# Logic.net
KiCad netlist of a schematic drawn in EAGLE
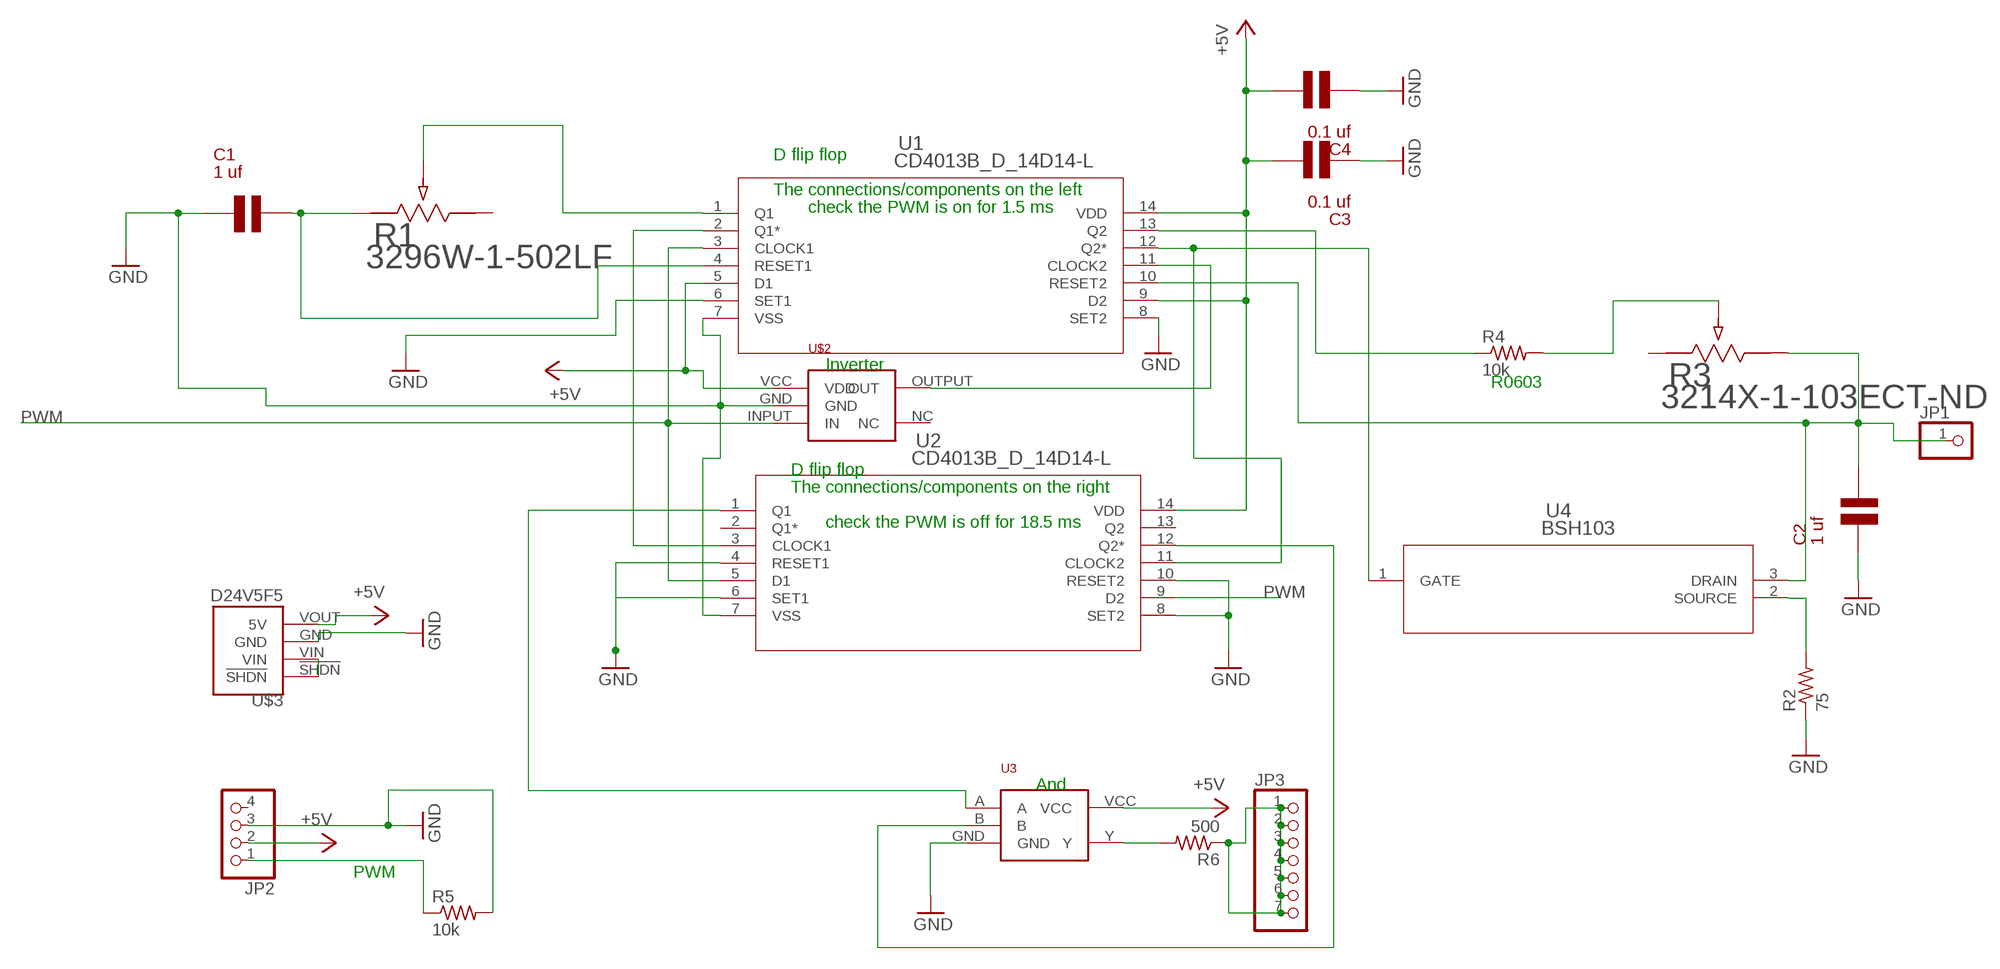
[diagram p0: schematic, sheet 1]

(export (version "E")
  (design (tool "Eeschema 10.0.6"))
  (components
    (comp (ref "C1")
      (value "1 uf")
      (footprint "eagle-import:X7R0805")
      (libsource (lib "eagle-import") (part "CER-CAP"))
    )
    (comp (ref "C2")
      (value "1 uf")
      (footprint "eagle-import:X7R0805")
      (libsource (lib "eagle-import") (part "CER-CAP"))
    )
    (comp (ref "C3")
      (value "0.1 uf")
      (footprint "eagle-import:X7R0805")
      (libsource (lib "eagle-import") (part "CER-CAP"))
    )
    (comp (ref "C4")
      (value "0.1 uf")
      (footprint "eagle-import:X7R0805")
      (libsource (lib "eagle-import") (part "CER-CAP"))
    )
    (comp (ref "JP1")
      (value "PINHD-1X1")
      (footprint "eagle-import:1X01")
      (libsource (lib "eagle-import") (part "PINHD-1X1"))
    )
    (comp (ref "JP2")
      (value "PINHD-1X4")
      (footprint "eagle-import:1X04")
      (libsource (lib "eagle-import") (part "PINHD-1X4"))
    )
    (comp (ref "JP3")
      (value "PINHD-1X7")
      (footprint "eagle-import:1X07")
      (libsource (lib "eagle-import") (part "PINHD-1X7"))
    )
    (comp (ref "R1")
      (value "3296W-1-502LF")
      (footprint "eagle-import:POT_3296W")
      (fields (field (name "MANUFACTURER_PART_NUMBER") "3296W1502LF"))
      (libsource (lib "eagle-import") (part "3296W-1-502LF"))
    )
    (comp (ref "R2")
      (value "75")
      (footprint "eagle-import:R0603")
      (libsource (lib "eagle-import") (part "R-US_R0603"))
    )
    (comp (ref "R3")
      (value "3214X-1-103ECT-ND")
      (footprint "eagle-import:POT_3214X")
      (libsource (lib "eagle-import") (part "3214X-1-103ECT-ND"))
    )
    (comp (ref "R4")
      (value "10k")
      (footprint "eagle-import:R0603")
      (libsource (lib "eagle-import") (part "R-US_R0603"))
    )
    (comp (ref "R5")
      (value "10k")
      (footprint "eagle-import:R0603")
      (libsource (lib "eagle-import") (part "R-US_R0603"))
    )
    (comp (ref "R6")
      (value "500")
      (footprint "eagle-import:R0603")
      (libsource (lib "eagle-import") (part "R-US_R0603"))
    )
    (comp (ref "U$2")
      (value "NCS704-INVERTER")
      (footprint "eagle-import:NC7S04-SOT23")
      (libsource (lib "eagle-import") (part "NCS704-INVERTER"))
    )
    (comp (ref "U$3")
      (value "D24V5F5")
      (footprint "eagle-import:D24V5FX_FLAT_THIN_R")
      (libsource (lib "eagle-import") (part "D24V5F5"))
    )
    (comp (ref "U1")
      (value "CD4013B_D_14D14-L")
      (footprint "eagle-import:D14-L")
      (libsource (lib "eagle-import") (part "CD4013B_D_14D14-L"))
    )
    (comp (ref "U2")
      (value "CD4013B_D_14D14-L")
      (footprint "eagle-import:D14-L")
      (libsource (lib "eagle-import") (part "CD4013B_D_14D14-L"))
    )
    (comp (ref "U3")
      (value "NC7SZ08-AND")
      (footprint "eagle-import:NC7S04-SOT23")
      (libsource (lib "eagle-import") (part "NC7SZ08-AND"))
    )
    (comp (ref "U4")
      (value "BSH103")
      (footprint "eagle-import:SOT23")
      (libsource (lib "eagle-import") (part "BSH103"))
    )
  )
  (nets
    (net (code "1") (name "+5V") (class "Default")
      (node (ref "C3") (pin "2") (pinfunction "2_2") (pintype "passive"))
      (node (ref "C4") (pin "2") (pinfunction "2_2") (pintype "passive"))
      (node (ref "JP2") (pin "2") (pinfunction "2_2") (pintype "passive"))
      (node (ref "U$2") (pin "VCC") (pinfunction "VDD_VCC") (pintype "power_in"))
      (node (ref "U$3") (pin "VOUT") (pinfunction "5V_VOUT") (pintype "bidirectional"))
      (node (ref "U1") (pin "14") (pinfunction "VDD_14") (pintype "power_in"))
      (node (ref "U1") (pin "5") (pinfunction "D1_5") (pintype "passive"))
      (node (ref "U1") (pin "9") (pinfunction "D2_9") (pintype "passive"))
      (node (ref "U2") (pin "14") (pinfunction "VDD_14") (pintype "power_in"))
      (node (ref "U3") (pin "VCC") (pinfunction "VCC_VCC") (pintype "power_in"))
    )
    (net (code "2") (name "/PWM") (class "Default")
      (node (ref "JP2") (pin "1") (pinfunction "1_1") (pintype "passive"))
      (node (ref "R5") (pin "1") (pinfunction "1_1") (pintype "passive"))
      (node (ref "U$2") (pin "INPUT") (pinfunction "IN_INPUT") (pintype "input"))
      (node (ref "U1") (pin "3") (pinfunction "CLOCK1_3") (pintype "passive"))
      (node (ref "U2") (pin "5") (pinfunction "D1_5") (pintype "passive"))
      (node (ref "U2") (pin "9") (pinfunction "D2_9") (pintype "passive"))
    )
    (net (code "3") (name "GND") (class "Default")
      (node (ref "C1") (pin "1") (pinfunction "1_1") (pintype "passive"))
      (node (ref "C2") (pin "1") (pinfunction "1_1") (pintype "passive"))
      (node (ref "C3") (pin "1") (pinfunction "1_1") (pintype "passive"))
      (node (ref "C4") (pin "1") (pinfunction "1_1") (pintype "passive"))
      (node (ref "JP2") (pin "3") (pinfunction "3_3") (pintype "passive"))
      (node (ref "R2") (pin "1") (pinfunction "1_1") (pintype "passive"))
      (node (ref "R5") (pin "2") (pinfunction "2_2") (pintype "passive"))
      (node (ref "U$2") (pin "GND") (pinfunction "GND_GND") (pintype "power_in"))
      (node (ref "U$3") (pin "GND") (pinfunction "GND_GND") (pintype "bidirectional"))
      (node (ref "U1") (pin "6") (pinfunction "SET1_6") (pintype "passive"))
      (node (ref "U1") (pin "7") (pinfunction "VSS_7") (pintype "power_in"))
      (node (ref "U1") (pin "8") (pinfunction "SET2_8") (pintype "passive"))
      (node (ref "U2") (pin "10") (pinfunction "RESET2_10") (pintype "passive"))
      (node (ref "U2") (pin "4") (pinfunction "RESET1_4") (pintype "passive"))
      (node (ref "U2") (pin "6") (pinfunction "SET1_6") (pintype "passive"))
      (node (ref "U2") (pin "7") (pinfunction "VSS_7") (pintype "power_in"))
      (node (ref "U2") (pin "8") (pinfunction "SET2_8") (pintype "passive"))
      (node (ref "U3") (pin "GND") (pinfunction "GND_GND") (pintype "power_in"))
    )
    (net (code "4") (name "Net-(JP3-Pad1)") (class "Default")
      (node (ref "JP3") (pin "1") (pinfunction "1_1") (pintype "passive"))
      (node (ref "JP3") (pin "2") (pinfunction "2_2") (pintype "passive"))
      (node (ref "JP3") (pin "3") (pinfunction "3_3") (pintype "passive"))
      (node (ref "JP3") (pin "4") (pinfunction "4_4") (pintype "passive"))
      (node (ref "JP3") (pin "5") (pinfunction "5_5") (pintype "passive"))
      (node (ref "JP3") (pin "6") (pinfunction "6_6") (pintype "passive"))
      (node (ref "JP3") (pin "7") (pinfunction "7_7") (pintype "passive"))
      (node (ref "R6") (pin "1") (pinfunction "1_1") (pintype "passive"))
    )
    (net (code "5") (name "Net-(R3-2)") (class "Default")
      (node (ref "R3") (pin "WIPER") (pinfunction "2_WIPER") (pintype "passive"))
      (node (ref "R4") (pin "2") (pinfunction "2_2") (pintype "passive"))
    )
    (net (code "6") (name "Net-(R3-3)") (class "Default")
      (node (ref "C2") (pin "2") (pinfunction "2_2") (pintype "passive"))
      (node (ref "JP1") (pin "1") (pinfunction "1_1") (pintype "passive"))
      (node (ref "R3") (pin "CW") (pinfunction "3_CW") (pintype "passive"))
      (node (ref "U1") (pin "10") (pinfunction "RESET2_10") (pintype "passive"))
      (node (ref "U4") (pin "3") (pinfunction "DRAIN_3") (pintype "passive"))
    )
    (net (code "7") (name "Net-(R6-Pad2)") (class "Default")
      (node (ref "R6") (pin "2") (pinfunction "2_2") (pintype "passive"))
      (node (ref "U3") (pin "Y") (pinfunction "Y_Y") (pintype "bidirectional"))
    )
    (net (code "8") (name "Net-(U$2-OUT)") (class "Default")
      (node (ref "U$2") (pin "OUTPUT") (pinfunction "OUT_OUTPUT") (pintype "output"))
      (node (ref "U1") (pin "11") (pinfunction "CLOCK2_11") (pintype "passive"))
    )
    (net (code "9") (name "Net-(U$3-~{SHDN})") (class "Default")
      (node (ref "U$3") (pin "!SHDN") (pinfunction "~{SHDN}_!SHDN") (pintype "bidirectional"))
      (node (ref "U$3") (pin "VIN") (pinfunction "VIN_VIN") (pintype "bidirectional"))
    )
    (net (code "10") (name "Net-(U1-Q1)") (class "Default")
      (node (ref "R1") (pin "2") (pinfunction "2_2") (pintype "passive"))
      (node (ref "U1") (pin "1") (pinfunction "Q1_1") (pintype "passive"))
    )
    (net (code "11") (name "Net-(U1-Q1*)") (class "Default")
      (node (ref "U1") (pin "2") (pinfunction "Q1*_2") (pintype "passive"))
      (node (ref "U2") (pin "3") (pinfunction "CLOCK1_3") (pintype "passive"))
    )
    (net (code "12") (name "Net-(U1-Q2)") (class "Default")
      (node (ref "R4") (pin "1") (pinfunction "1_1") (pintype "passive"))
      (node (ref "U1") (pin "13") (pinfunction "Q2_13") (pintype "passive"))
    )
    (net (code "13") (name "Net-(U1-Q2*)") (class "Default")
      (node (ref "U1") (pin "12") (pinfunction "Q2*_12") (pintype "passive"))
      (node (ref "U2") (pin "11") (pinfunction "CLOCK2_11") (pintype "passive"))
      (node (ref "U4") (pin "1") (pinfunction "GATE_1") (pintype "passive"))
    )
    (net (code "14") (name "Net-(U1-RESET1)") (class "Default")
      (node (ref "C1") (pin "2") (pinfunction "2_2") (pintype "passive"))
      (node (ref "R1") (pin "1") (pinfunction "1_1") (pintype "passive"))
      (node (ref "U1") (pin "4") (pinfunction "RESET1_4") (pintype "passive"))
    )
    (net (code "15") (name "Net-(U2-Q1)") (class "Default")
      (node (ref "U2") (pin "1") (pinfunction "Q1_1") (pintype "passive"))
      (node (ref "U3") (pin "A") (pinfunction "A_A") (pintype "power_in"))
    )
    (net (code "16") (name "Net-(U2-Q2*)") (class "Default")
      (node (ref "U2") (pin "12") (pinfunction "Q2*_12") (pintype "passive"))
      (node (ref "U3") (pin "B") (pinfunction "B_B") (pintype "power_in"))
    )
    (net (code "17") (name "Net-(U4-SOURCE)") (class "Default")
      (node (ref "R2") (pin "2") (pinfunction "2_2") (pintype "passive"))
      (node (ref "U4") (pin "2") (pinfunction "SOURCE_2") (pintype "passive"))
    )
    (net (code "18") (name "unconnected-(JP2-Pad4)") (class "Default")
      (node (ref "JP2") (pin "4") (pinfunction "4_4") (pintype "passive"))
    )
    (net (code "19") (name "unconnected-(R1-Pad3)") (class "Default")
      (node (ref "R1") (pin "3") (pinfunction "3_3") (pintype "passive"))
    )
    (net (code "20") (name "unconnected-(R3-1-PadCCW)") (class "Default")
      (node (ref "R3") (pin "CCW") (pinfunction "1_CCW") (pintype "passive"))
    )
    (net (code "21") (name "unconnected-(U$2-PadNC)") (class "Default")
      (node (ref "U$2") (pin "NC") (pinfunction "NC_NC") (pintype "bidirectional"))
    )
    (net (code "22") (name "unconnected-(U2-Q1*-Pad2)") (class "Default")
      (node (ref "U2") (pin "2") (pinfunction "Q1*_2") (pintype "passive"))
    )
    (net (code "23") (name "unconnected-(U2-Q2-Pad13)") (class "Default")
      (node (ref "U2") (pin "13") (pinfunction "Q2_13") (pintype "passive"))
    )
  )
)
